# bigsegment.net
KiCad netlist of a schematic drawn in Altium Designer
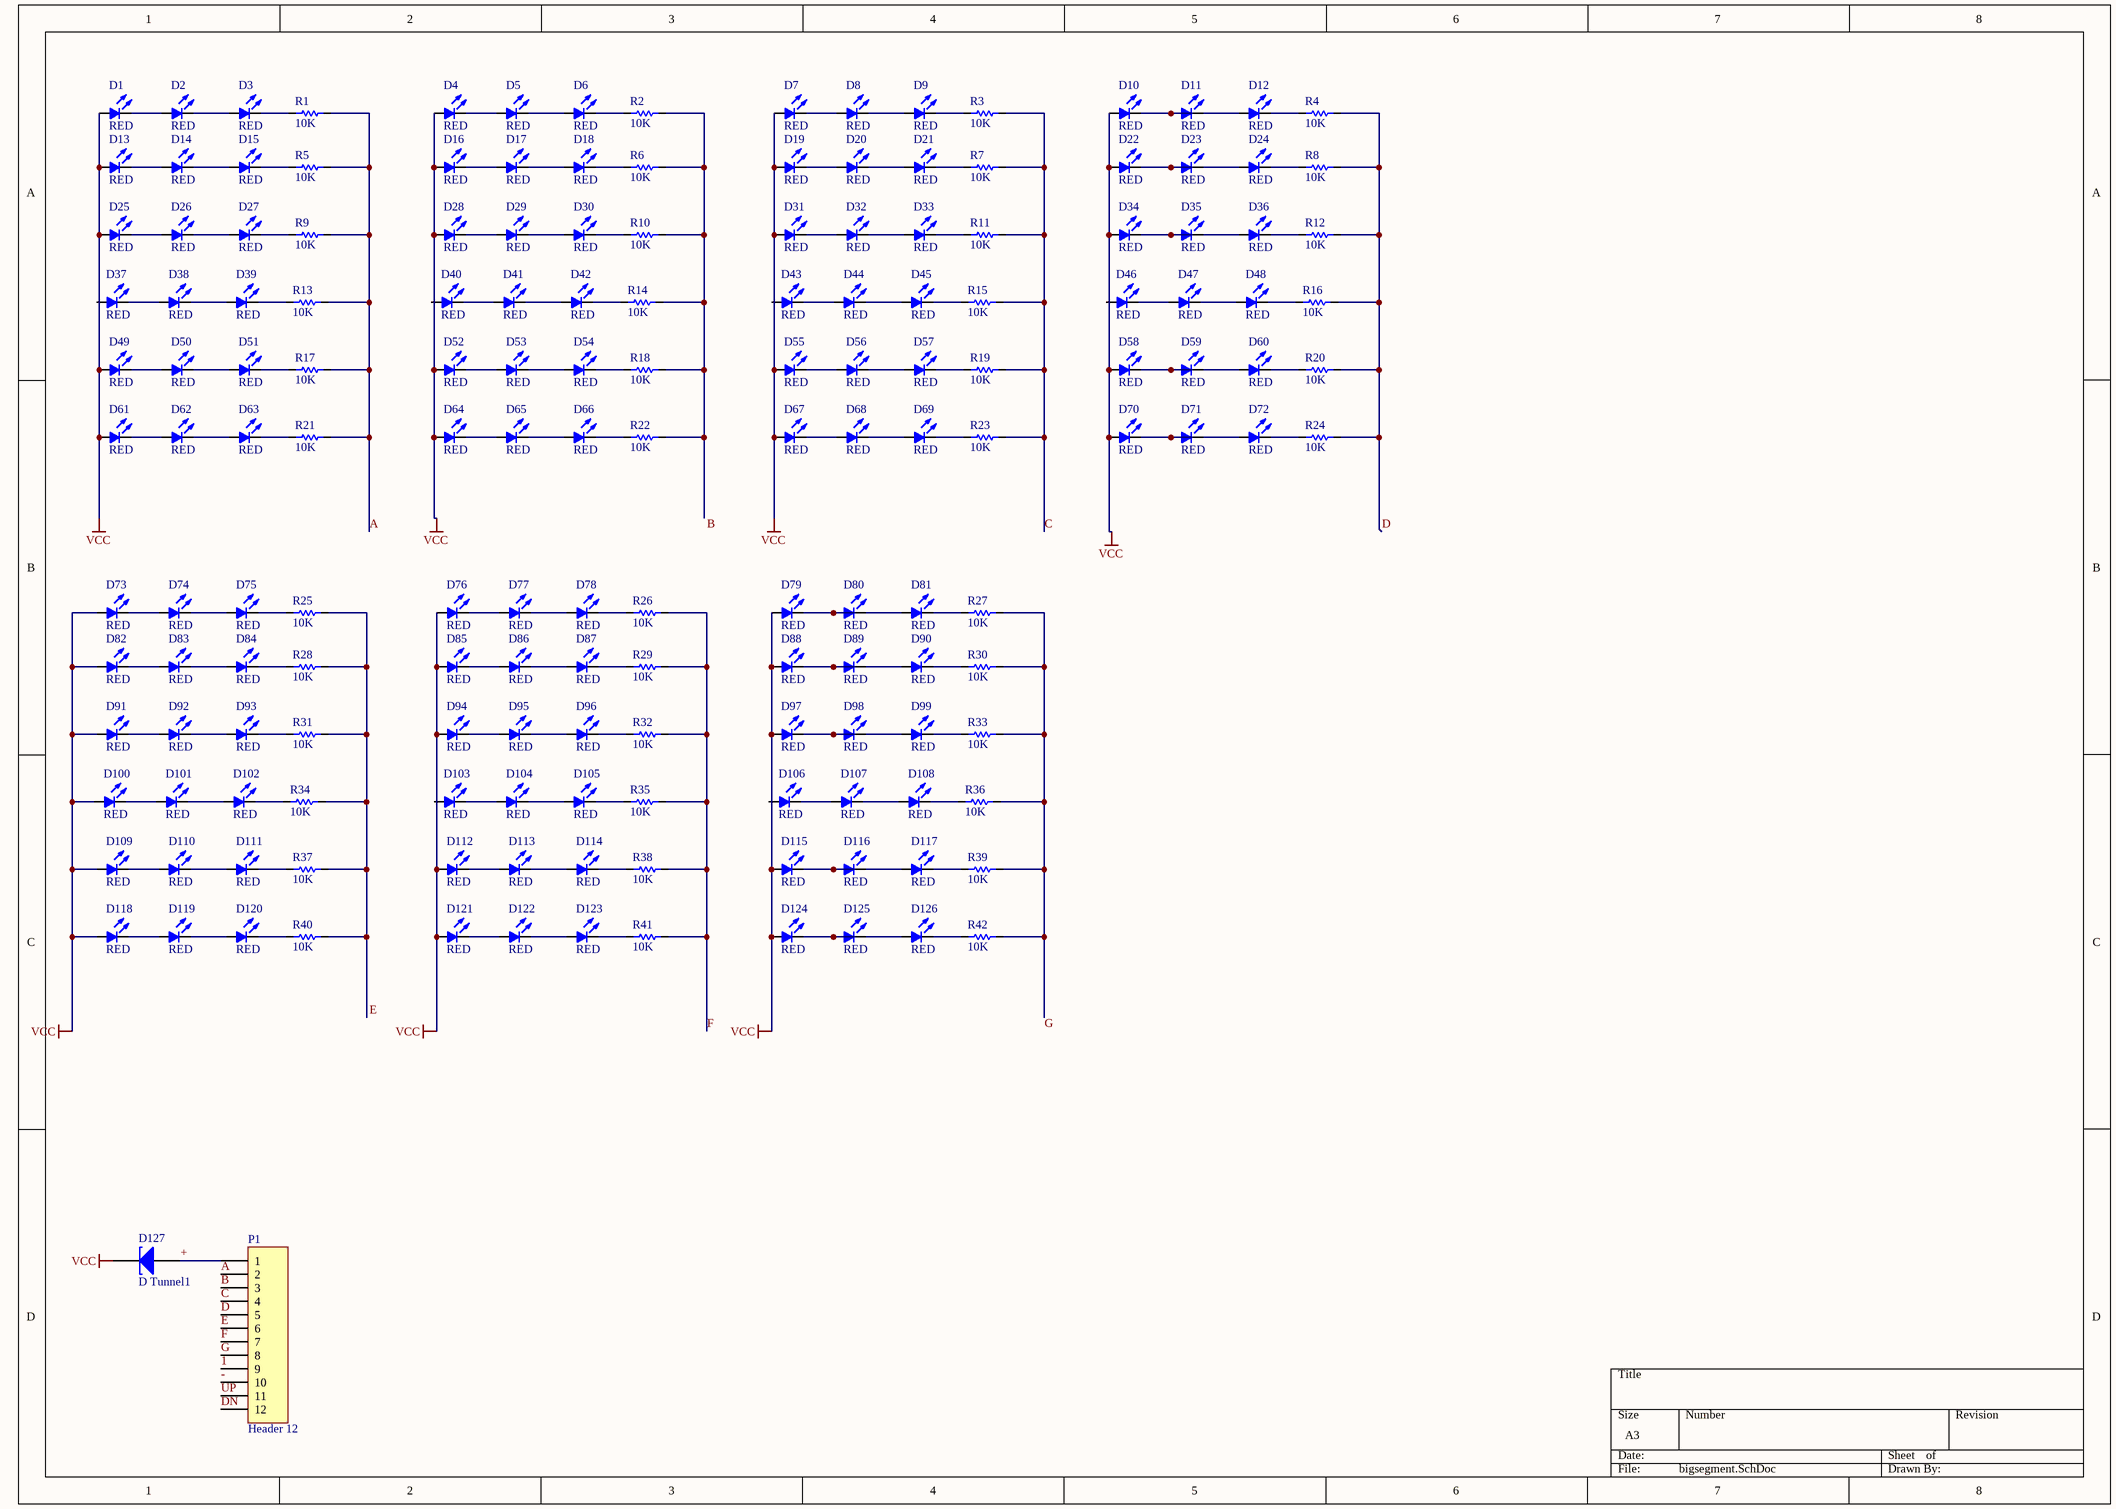
[diagram p0: bigsegment.SchDoc]

(export (version "E")
  (design (tool "Eeschema 10.0.6"))
  (components
    (comp (ref "D1")
      (value "MODEL")
      (footprint "RES 0805 (2012X06L)")
      (description "Typical LED")
      (fields (field (name "COLOR") "RED"))
      (libsource (lib "AltiumLib1") (part "LED 5mm"))
    )
    (comp (ref "D2")
      (value "MODEL")
      (footprint "RES 0805 (2012X06L)")
      (description "Typical LED")
      (fields (field (name "COLOR") "RED"))
      (libsource (lib "AltiumLib1") (part "LED 5mm"))
    )
    (comp (ref "D3")
      (value "MODEL")
      (footprint "RES 0805 (2012X06L)")
      (description "Typical LED")
      (fields (field (name "COLOR") "RED"))
      (libsource (lib "AltiumLib1") (part "LED 5mm"))
    )
    (comp (ref "D4")
      (value "MODEL")
      (footprint "RES 0805 (2012X06L)")
      (description "Typical LED")
      (fields (field (name "COLOR") "RED"))
      (libsource (lib "AltiumLib1") (part "LED 5mm"))
    )
    (comp (ref "D5")
      (value "MODEL")
      (footprint "RES 0805 (2012X06L)")
      (description "Typical LED")
      (fields (field (name "COLOR") "RED"))
      (libsource (lib "AltiumLib1") (part "LED 5mm"))
    )
    (comp (ref "D6")
      (value "MODEL")
      (footprint "RES 0805 (2012X06L)")
      (description "Typical LED")
      (fields (field (name "COLOR") "RED"))
      (libsource (lib "AltiumLib1") (part "LED 5mm"))
    )
    (comp (ref "D7")
      (value "MODEL")
      (footprint "RES 0805 (2012X06L)")
      (description "Typical LED")
      (fields (field (name "COLOR") "RED"))
      (libsource (lib "AltiumLib1") (part "LED 5mm"))
    )
    (comp (ref "D8")
      (value "MODEL")
      (footprint "RES 0805 (2012X06L)")
      (description "Typical LED")
      (fields (field (name "COLOR") "RED"))
      (libsource (lib "AltiumLib1") (part "LED 5mm"))
    )
    (comp (ref "D9")
      (value "MODEL")
      (footprint "RES 0805 (2012X06L)")
      (description "Typical LED")
      (fields (field (name "COLOR") "RED"))
      (libsource (lib "AltiumLib1") (part "LED 5mm"))
    )
    (comp (ref "D10")
      (value "MODEL")
      (footprint "RES 0805 (2012X06L)")
      (description "Typical LED")
      (fields (field (name "COLOR") "RED"))
      (libsource (lib "AltiumLib1") (part "LED 5mm"))
    )
    (comp (ref "D11")
      (value "MODEL")
      (footprint "RES 0805 (2012X06L)")
      (description "Typical LED")
      (fields (field (name "COLOR") "RED"))
      (libsource (lib "AltiumLib1") (part "LED 5mm"))
    )
    (comp (ref "D12")
      (value "MODEL")
      (footprint "RES 0805 (2012X06L)")
      (description "Typical LED")
      (fields (field (name "COLOR") "RED"))
      (libsource (lib "AltiumLib1") (part "LED 5mm"))
    )
    (comp (ref "D13")
      (value "MODEL")
      (footprint "RES 0805 (2012X06L)")
      (description "Typical LED")
      (fields (field (name "COLOR") "RED"))
      (libsource (lib "AltiumLib1") (part "LED 5mm"))
    )
    (comp (ref "D14")
      (value "MODEL")
      (footprint "RES 0805 (2012X06L)")
      (description "Typical LED")
      (fields (field (name "COLOR") "RED"))
      (libsource (lib "AltiumLib1") (part "LED 5mm"))
    )
    (comp (ref "D15")
      (value "MODEL")
      (footprint "RES 0805 (2012X06L)")
      (description "Typical LED")
      (fields (field (name "COLOR") "RED"))
      (libsource (lib "AltiumLib1") (part "LED 5mm"))
    )
    (comp (ref "D16")
      (value "MODEL")
      (footprint "RES 0805 (2012X06L)")
      (description "Typical LED")
      (fields (field (name "COLOR") "RED"))
      (libsource (lib "AltiumLib1") (part "LED 5mm"))
    )
    (comp (ref "D17")
      (value "MODEL")
      (footprint "RES 0805 (2012X06L)")
      (description "Typical LED")
      (fields (field (name "COLOR") "RED"))
      (libsource (lib "AltiumLib1") (part "LED 5mm"))
    )
    (comp (ref "D18")
      (value "MODEL")
      (footprint "RES 0805 (2012X06L)")
      (description "Typical LED")
      (fields (field (name "COLOR") "RED"))
      (libsource (lib "AltiumLib1") (part "LED 5mm"))
    )
    (comp (ref "D19")
      (value "MODEL")
      (footprint "RES 0805 (2012X06L)")
      (description "Typical LED")
      (fields (field (name "COLOR") "RED"))
      (libsource (lib "AltiumLib1") (part "LED 5mm"))
    )
    (comp (ref "D20")
      (value "MODEL")
      (footprint "RES 0805 (2012X06L)")
      (description "Typical LED")
      (fields (field (name "COLOR") "RED"))
      (libsource (lib "AltiumLib1") (part "LED 5mm"))
    )
    (comp (ref "D21")
      (value "MODEL")
      (footprint "RES 0805 (2012X06L)")
      (description "Typical LED")
      (fields (field (name "COLOR") "RED"))
      (libsource (lib "AltiumLib1") (part "LED 5mm"))
    )
    (comp (ref "D22")
      (value "MODEL")
      (footprint "RES 0805 (2012X06L)")
      (description "Typical LED")
      (fields (field (name "COLOR") "RED"))
      (libsource (lib "AltiumLib1") (part "LED 5mm"))
    )
    (comp (ref "D23")
      (value "MODEL")
      (footprint "RES 0805 (2012X06L)")
      (description "Typical LED")
      (fields (field (name "COLOR") "RED"))
      (libsource (lib "AltiumLib1") (part "LED 5mm"))
    )
    (comp (ref "D24")
      (value "MODEL")
      (footprint "RES 0805 (2012X06L)")
      (description "Typical LED")
      (fields (field (name "COLOR") "RED"))
      (libsource (lib "AltiumLib1") (part "LED 5mm"))
    )
    (comp (ref "D25")
      (value "MODEL")
      (footprint "RES 0805 (2012X06L)")
      (description "Typical LED")
      (fields (field (name "COLOR") "RED"))
      (libsource (lib "AltiumLib1") (part "LED 5mm"))
    )
    (comp (ref "D26")
      (value "MODEL")
      (footprint "RES 0805 (2012X06L)")
      (description "Typical LED")
      (fields (field (name "COLOR") "RED"))
      (libsource (lib "AltiumLib1") (part "LED 5mm"))
    )
    (comp (ref "D27")
      (value "MODEL")
      (footprint "RES 0805 (2012X06L)")
      (description "Typical LED")
      (fields (field (name "COLOR") "RED"))
      (libsource (lib "AltiumLib1") (part "LED 5mm"))
    )
    (comp (ref "D28")
      (value "MODEL")
      (footprint "RES 0805 (2012X06L)")
      (description "Typical LED")
      (fields (field (name "COLOR") "RED"))
      (libsource (lib "AltiumLib1") (part "LED 5mm"))
    )
    (comp (ref "D29")
      (value "MODEL")
      (footprint "RES 0805 (2012X06L)")
      (description "Typical LED")
      (fields (field (name "COLOR") "RED"))
      (libsource (lib "AltiumLib1") (part "LED 5mm"))
    )
    (comp (ref "D30")
      (value "MODEL")
      (footprint "RES 0805 (2012X06L)")
      (description "Typical LED")
      (fields (field (name "COLOR") "RED"))
      (libsource (lib "AltiumLib1") (part "LED 5mm"))
    )
    (comp (ref "D31")
      (value "MODEL")
      (footprint "RES 0805 (2012X06L)")
      (description "Typical LED")
      (fields (field (name "COLOR") "RED"))
      (libsource (lib "AltiumLib1") (part "LED 5mm"))
    )
    (comp (ref "D32")
      (value "MODEL")
      (footprint "RES 0805 (2012X06L)")
      (description "Typical LED")
      (fields (field (name "COLOR") "RED"))
      (libsource (lib "AltiumLib1") (part "LED 5mm"))
    )
    (comp (ref "D33")
      (value "MODEL")
      (footprint "RES 0805 (2012X06L)")
      (description "Typical LED")
      (fields (field (name "COLOR") "RED"))
      (libsource (lib "AltiumLib1") (part "LED 5mm"))
    )
    (comp (ref "D34")
      (value "MODEL")
      (footprint "RES 0805 (2012X06L)")
      (description "Typical LED")
      (fields (field (name "COLOR") "RED"))
      (libsource (lib "AltiumLib1") (part "LED 5mm"))
    )
    (comp (ref "D35")
      (value "MODEL")
      (footprint "RES 0805 (2012X06L)")
      (description "Typical LED")
      (fields (field (name "COLOR") "RED"))
      (libsource (lib "AltiumLib1") (part "LED 5mm"))
    )
    (comp (ref "D36")
      (value "MODEL")
      (footprint "RES 0805 (2012X06L)")
      (description "Typical LED")
      (fields (field (name "COLOR") "RED"))
      (libsource (lib "AltiumLib1") (part "LED 5mm"))
    )
    (comp (ref "D37")
      (value "MODEL")
      (footprint "RES 0805 (2012X06L)")
      (description "Typical LED")
      (fields (field (name "COLOR") "RED"))
      (libsource (lib "AltiumLib1") (part "LED 5mm"))
    )
    (comp (ref "D38")
      (value "MODEL")
      (footprint "RES 0805 (2012X06L)")
      (description "Typical LED")
      (fields (field (name "COLOR") "RED"))
      (libsource (lib "AltiumLib1") (part "LED 5mm"))
    )
    (comp (ref "D39")
      (value "MODEL")
      (footprint "RES 0805 (2012X06L)")
      (description "Typical LED")
      (fields (field (name "COLOR") "RED"))
      (libsource (lib "AltiumLib1") (part "LED 5mm"))
    )
    (comp (ref "D40")
      (value "MODEL")
      (footprint "RES 0805 (2012X06L)")
      (description "Typical LED")
      (fields (field (name "COLOR") "RED"))
      (libsource (lib "AltiumLib1") (part "LED 5mm"))
    )
    (comp (ref "D41")
      (value "MODEL")
      (footprint "RES 0805 (2012X06L)")
      (description "Typical LED")
      (fields (field (name "COLOR") "RED"))
      (libsource (lib "AltiumLib1") (part "LED 5mm"))
    )
    (comp (ref "D42")
      (value "MODEL")
      (footprint "RES 0805 (2012X06L)")
      (description "Typical LED")
      (fields (field (name "COLOR") "RED"))
      (libsource (lib "AltiumLib1") (part "LED 5mm"))
    )
    (comp (ref "D43")
      (value "MODEL")
      (footprint "RES 0805 (2012X06L)")
      (description "Typical LED")
      (fields (field (name "COLOR") "RED"))
      (libsource (lib "AltiumLib1") (part "LED 5mm"))
    )
    (comp (ref "D44")
      (value "MODEL")
      (footprint "RES 0805 (2012X06L)")
      (description "Typical LED")
      (fields (field (name "COLOR") "RED"))
      (libsource (lib "AltiumLib1") (part "LED 5mm"))
    )
    (comp (ref "D45")
      (value "MODEL")
      (footprint "RES 0805 (2012X06L)")
      (description "Typical LED")
      (fields (field (name "COLOR") "RED"))
      (libsource (lib "AltiumLib1") (part "LED 5mm"))
    )
    (comp (ref "D46")
      (value "MODEL")
      (footprint "RES 0805 (2012X06L)")
      (description "Typical LED")
      (fields (field (name "COLOR") "RED"))
      (libsource (lib "AltiumLib1") (part "LED 5mm"))
    )
    (comp (ref "D47")
      (value "MODEL")
      (footprint "RES 0805 (2012X06L)")
      (description "Typical LED")
      (fields (field (name "COLOR") "RED"))
      (libsource (lib "AltiumLib1") (part "LED 5mm"))
    )
    (comp (ref "D48")
      (value "MODEL")
      (footprint "RES 0805 (2012X06L)")
      (description "Typical LED")
      (fields (field (name "COLOR") "RED"))
      (libsource (lib "AltiumLib1") (part "LED 5mm"))
    )
    (comp (ref "D49")
      (value "MODEL")
      (footprint "RES 0805 (2012X06L)")
      (description "Typical LED")
      (fields (field (name "COLOR") "RED"))
      (libsource (lib "AltiumLib1") (part "LED 5mm"))
    )
    (comp (ref "D50")
      (value "MODEL")
      (footprint "RES 0805 (2012X06L)")
      (description "Typical LED")
      (fields (field (name "COLOR") "RED"))
      (libsource (lib "AltiumLib1") (part "LED 5mm"))
    )
    (comp (ref "D51")
      (value "MODEL")
      (footprint "RES 0805 (2012X06L)")
      (description "Typical LED")
      (fields (field (name "COLOR") "RED"))
      (libsource (lib "AltiumLib1") (part "LED 5mm"))
    )
    (comp (ref "D52")
      (value "MODEL")
      (footprint "RES 0805 (2012X06L)")
      (description "Typical LED")
      (fields (field (name "COLOR") "RED"))
      (libsource (lib "AltiumLib1") (part "LED 5mm"))
    )
    (comp (ref "D53")
      (value "MODEL")
      (footprint "RES 0805 (2012X06L)")
      (description "Typical LED")
      (fields (field (name "COLOR") "RED"))
      (libsource (lib "AltiumLib1") (part "LED 5mm"))
    )
    (comp (ref "D54")
      (value "MODEL")
      (footprint "RES 0805 (2012X06L)")
      (description "Typical LED")
      (fields (field (name "COLOR") "RED"))
      (libsource (lib "AltiumLib1") (part "LED 5mm"))
    )
    (comp (ref "D55")
      (value "MODEL")
      (footprint "RES 0805 (2012X06L)")
      (description "Typical LED")
      (fields (field (name "COLOR") "RED"))
      (libsource (lib "AltiumLib1") (part "LED 5mm"))
    )
    (comp (ref "D56")
      (value "MODEL")
      (footprint "RES 0805 (2012X06L)")
      (description "Typical LED")
      (fields (field (name "COLOR") "RED"))
      (libsource (lib "AltiumLib1") (part "LED 5mm"))
    )
    (comp (ref "D57")
      (value "MODEL")
      (footprint "RES 0805 (2012X06L)")
      (description "Typical LED")
      (fields (field (name "COLOR") "RED"))
      (libsource (lib "AltiumLib1") (part "LED 5mm"))
    )
    (comp (ref "D58")
      (value "MODEL")
      (footprint "RES 0805 (2012X06L)")
      (description "Typical LED")
      (fields (field (name "COLOR") "RED"))
      (libsource (lib "AltiumLib1") (part "LED 5mm"))
    )
    (comp (ref "D59")
      (value "MODEL")
      (footprint "RES 0805 (2012X06L)")
      (description "Typical LED")
      (fields (field (name "COLOR") "RED"))
      (libsource (lib "AltiumLib1") (part "LED 5mm"))
    )
    (comp (ref "D60")
      (value "MODEL")
      (footprint "RES 0805 (2012X06L)")
      (description "Typical LED")
      (fields (field (name "COLOR") "RED"))
      (libsource (lib "AltiumLib1") (part "LED 5mm"))
    )
    (comp (ref "D61")
      (value "MODEL")
      (footprint "RES 0805 (2012X06L)")
      (description "Typical LED")
      (fields (field (name "COLOR") "RED"))
      (libsource (lib "AltiumLib1") (part "LED 5mm"))
    )
    (comp (ref "D62")
      (value "MODEL")
      (footprint "RES 0805 (2012X06L)")
      (description "Typical LED")
      (fields (field (name "COLOR") "RED"))
      (libsource (lib "AltiumLib1") (part "LED 5mm"))
    )
    (comp (ref "D63")
      (value "MODEL")
      (footprint "RES 0805 (2012X06L)")
      (description "Typical LED")
      (fields (field (name "COLOR") "RED"))
      (libsource (lib "AltiumLib1") (part "LED 5mm"))
    )
    (comp (ref "D64")
      (value "MODEL")
      (footprint "RES 0805 (2012X06L)")
      (description "Typical LED")
      (fields (field (name "COLOR") "RED"))
      (libsource (lib "AltiumLib1") (part "LED 5mm"))
    )
    (comp (ref "D65")
      (value "MODEL")
      (footprint "RES 0805 (2012X06L)")
      (description "Typical LED")
      (fields (field (name "COLOR") "RED"))
      (libsource (lib "AltiumLib1") (part "LED 5mm"))
    )
    (comp (ref "D66")
      (value "MODEL")
      (footprint "RES 0805 (2012X06L)")
      (description "Typical LED")
      (fields (field (name "COLOR") "RED"))
      (libsource (lib "AltiumLib1") (part "LED 5mm"))
    )
    (comp (ref "D67")
      (value "MODEL")
      (footprint "RES 0805 (2012X06L)")
      (description "Typical LED")
      (fields (field (name "COLOR") "RED"))
      (libsource (lib "AltiumLib1") (part "LED 5mm"))
    )
    (comp (ref "D68")
      (value "MODEL")
      (footprint "RES 0805 (2012X06L)")
      (description "Typical LED")
      (fields (field (name "COLOR") "RED"))
      (libsource (lib "AltiumLib1") (part "LED 5mm"))
    )
    (comp (ref "D69")
      (value "MODEL")
      (footprint "RES 0805 (2012X06L)")
      (description "Typical LED")
      (fields (field (name "COLOR") "RED"))
      (libsource (lib "AltiumLib1") (part "LED 5mm"))
    )
    (comp (ref "D70")
      (value "MODEL")
      (footprint "RES 0805 (2012X06L)")
      (description "Typical LED")
      (fields (field (name "COLOR") "RED"))
      (libsource (lib "AltiumLib1") (part "LED 5mm"))
    )
    (comp (ref "D71")
      (value "MODEL")
      (footprint "RES 0805 (2012X06L)")
      (description "Typical LED")
      (fields (field (name "COLOR") "RED"))
      (libsource (lib "AltiumLib1") (part "LED 5mm"))
    )
    (comp (ref "D72")
      (value "MODEL")
      (footprint "RES 0805 (2012X06L)")
      (description "Typical LED")
      (fields (field (name "COLOR") "RED"))
      (libsource (lib "AltiumLib1") (part "LED 5mm"))
    )
    (comp (ref "D73")
      (value "MODEL")
      (footprint "RES 0805 (2012X06L)")
      (description "Typical LED")
      (fields (field (name "COLOR") "RED"))
      (libsource (lib "AltiumLib1") (part "LED 5mm"))
    )
    (comp (ref "D74")
      (value "MODEL")
      (footprint "RES 0805 (2012X06L)")
      (description "Typical LED")
      (fields (field (name "COLOR") "RED"))
      (libsource (lib "AltiumLib1") (part "LED 5mm"))
    )
    (comp (ref "D75")
      (value "MODEL")
      (footprint "RES 0805 (2012X06L)")
      (description "Typical LED")
      (fields (field (name "COLOR") "RED"))
      (libsource (lib "AltiumLib1") (part "LED 5mm"))
    )
    (comp (ref "D76")
      (value "MODEL")
      (footprint "RES 0805 (2012X06L)")
      (description "Typical LED")
      (fields (field (name "COLOR") "RED"))
      (libsource (lib "AltiumLib1") (part "LED 5mm"))
    )
    (comp (ref "D77")
      (value "MODEL")
      (footprint "RES 0805 (2012X06L)")
      (description "Typical LED")
      (fields (field (name "COLOR") "RED"))
      (libsource (lib "AltiumLib1") (part "LED 5mm"))
    )
    (comp (ref "D78")
      (value "MODEL")
      (footprint "RES 0805 (2012X06L)")
      (description "Typical LED")
      (fields (field (name "COLOR") "RED"))
      (libsource (lib "AltiumLib1") (part "LED 5mm"))
    )
    (comp (ref "D79")
      (value "MODEL")
      (footprint "RES 0805 (2012X06L)")
      (description "Typical LED")
      (fields (field (name "COLOR") "RED"))
      (libsource (lib "AltiumLib1") (part "LED 5mm"))
    )
    (comp (ref "D80")
      (value "MODEL")
      (footprint "RES 0805 (2012X06L)")
      (description "Typical LED")
      (fields (field (name "COLOR") "RED"))
      (libsource (lib "AltiumLib1") (part "LED 5mm"))
    )
    (comp (ref "D81")
      (value "MODEL")
      (footprint "RES 0805 (2012X06L)")
      (description "Typical LED")
      (fields (field (name "COLOR") "RED"))
      (libsource (lib "AltiumLib1") (part "LED 5mm"))
    )
    (comp (ref "D82")
      (value "MODEL")
      (footprint "RES 0805 (2012X06L)")
      (description "Typical LED")
      (fields (field (name "COLOR") "RED"))
      (libsource (lib "AltiumLib1") (part "LED 5mm"))
    )
    (comp (ref "D83")
      (value "MODEL")
      (footprint "RES 0805 (2012X06L)")
      (description "Typical LED")
      (fields (field (name "COLOR") "RED"))
      (libsource (lib "AltiumLib1") (part "LED 5mm"))
    )
    (comp (ref "D84")
      (value "MODEL")
      (footprint "RES 0805 (2012X06L)")
      (description "Typical LED")
      (fields (field (name "COLOR") "RED"))
      (libsource (lib "AltiumLib1") (part "LED 5mm"))
    )
    (comp (ref "D85")
      (value "MODEL")
      (footprint "RES 0805 (2012X06L)")
      (description "Typical LED")
      (fields (field (name "COLOR") "RED"))
      (libsource (lib "AltiumLib1") (part "LED 5mm"))
    )
    (comp (ref "D86")
      (value "MODEL")
      (footprint "RES 0805 (2012X06L)")
      (description "Typical LED")
      (fields (field (name "COLOR") "RED"))
      (libsource (lib "AltiumLib1") (part "LED 5mm"))
    )
    (comp (ref "D87")
      (value "MODEL")
      (footprint "RES 0805 (2012X06L)")
      (description "Typical LED")
      (fields (field (name "COLOR") "RED"))
      (libsource (lib "AltiumLib1") (part "LED 5mm"))
    )
    (comp (ref "D88")
      (value "MODEL")
      (footprint "RES 0805 (2012X06L)")
      (description "Typical LED")
      (fields (field (name "COLOR") "RED"))
      (libsource (lib "AltiumLib1") (part "LED 5mm"))
    )
    (comp (ref "D89")
      (value "MODEL")
      (footprint "RES 0805 (2012X06L)")
      (description "Typical LED")
      (fields (field (name "COLOR") "RED"))
      (libsource (lib "AltiumLib1") (part "LED 5mm"))
    )
    (comp (ref "D90")
      (value "MODEL")
      (footprint "RES 0805 (2012X06L)")
      (description "Typical LED")
      (fields (field (name "COLOR") "RED"))
      (libsource (lib "AltiumLib1") (part "LED 5mm"))
    )
    (comp (ref "D91")
      (value "MODEL")
      (footprint "RES 0805 (2012X06L)")
      (description "Typical LED")
      (fields (field (name "COLOR") "RED"))
      (libsource (lib "AltiumLib1") (part "LED 5mm"))
    )
    (comp (ref "D92")
      (value "MODEL")
      (footprint "RES 0805 (2012X06L)")
      (description "Typical LED")
      (fields (field (name "COLOR") "RED"))
      (libsource (lib "AltiumLib1") (part "LED 5mm"))
    )
    (comp (ref "D93")
      (value "MODEL")
      (footprint "RES 0805 (2012X06L)")
      (description "Typical LED")
      (fields (field (name "COLOR") "RED"))
      (libsource (lib "AltiumLib1") (part "LED 5mm"))
    )
    (comp (ref "D94")
      (value "MODEL")
      (footprint "RES 0805 (2012X06L)")
      (description "Typical LED")
      (fields (field (name "COLOR") "RED"))
      (libsource (lib "AltiumLib1") (part "LED 5mm"))
    )
    (comp (ref "D95")
      (value "MODEL")
      (footprint "RES 0805 (2012X06L)")
      (description "Typical LED")
      (fields (field (name "COLOR") "RED"))
      (libsource (lib "AltiumLib1") (part "LED 5mm"))
    )
    (comp (ref "D96")
      (value "MODEL")
      (footprint "RES 0805 (2012X06L)")
      (description "Typical LED")
      (fields (field (name "COLOR") "RED"))
      (libsource (lib "AltiumLib1") (part "LED 5mm"))
    )
    (comp (ref "D97")
      (value "MODEL")
      (footprint "RES 0805 (2012X06L)")
      (description "Typical LED")
      (fields (field (name "COLOR") "RED"))
      (libsource (lib "AltiumLib1") (part "LED 5mm"))
    )
    (comp (ref "D98")
      (value "MODEL")
      (footprint "RES 0805 (2012X06L)")
      (description "Typical LED")
      (fields (field (name "COLOR") "RED"))
      (libsource (lib "AltiumLib1") (part "LED 5mm"))
    )
    (comp (ref "D99")
      (value "MODEL")
      (footprint "RES 0805 (2012X06L)")
      (description "Typical LED")
      (fields (field (name "COLOR") "RED"))
      (libsource (lib "AltiumLib1") (part "LED 5mm"))
    )
    (comp (ref "D100")
      (value "MODEL")
      (footprint "RES 0805 (2012X06L)")
      (description "Typical LED")
      (fields (field (name "COLOR") "RED"))
      (libsource (lib "AltiumLib1") (part "LED 5mm"))
    )
    (comp (ref "D101")
      (value "MODEL")
      (footprint "RES 0805 (2012X06L)")
      (description "Typical LED")
      (fields (field (name "COLOR") "RED"))
      (libsource (lib "AltiumLib1") (part "LED 5mm"))
    )
    (comp (ref "D102")
      (value "MODEL")
      (footprint "RES 0805 (2012X06L)")
      (description "Typical LED")
      (fields (field (name "COLOR") "RED"))
      (libsource (lib "AltiumLib1") (part "LED 5mm"))
    )
    (comp (ref "D103")
      (value "MODEL")
      (footprint "RES 0805 (2012X06L)")
      (description "Typical LED")
      (fields (field (name "COLOR") "RED"))
      (libsource (lib "AltiumLib1") (part "LED 5mm"))
    )
    (comp (ref "D104")
      (value "MODEL")
      (footprint "RES 0805 (2012X06L)")
      (description "Typical LED")
      (fields (field (name "COLOR") "RED"))
      (libsource (lib "AltiumLib1") (part "LED 5mm"))
    )
    (comp (ref "D105")
      (value "MODEL")
      (footprint "RES 0805 (2012X06L)")
      (description "Typical LED")
      (fields (field (name "COLOR") "RED"))
      (libsource (lib "AltiumLib1") (part "LED 5mm"))
    )
    (comp (ref "D106")
      (value "MODEL")
      (footprint "RES 0805 (2012X06L)")
      (description "Typical LED")
      (fields (field (name "COLOR") "RED"))
      (libsource (lib "AltiumLib1") (part "LED 5mm"))
    )
    (comp (ref "D107")
      (value "MODEL")
      (footprint "RES 0805 (2012X06L)")
      (description "Typical LED")
      (fields (field (name "COLOR") "RED"))
      (libsource (lib "AltiumLib1") (part "LED 5mm"))
    )
    (comp (ref "D108")
      (value "MODEL")
      (footprint "RES 0805 (2012X06L)")
      (description "Typical LED")
      (fields (field (name "COLOR") "RED"))
      (libsource (lib "AltiumLib1") (part "LED 5mm"))
    )
    (comp (ref "D109")
      (value "MODEL")
      (footprint "RES 0805 (2012X06L)")
      (description "Typical LED")
      (fields (field (name "COLOR") "RED"))
      (libsource (lib "AltiumLib1") (part "LED 5mm"))
    )
    (comp (ref "D110")
      (value "MODEL")
      (footprint "RES 0805 (2012X06L)")
      (description "Typical LED")
      (fields (field (name "COLOR") "RED"))
      (libsource (lib "AltiumLib1") (part "LED 5mm"))
    )
    (comp (ref "D111")
      (value "MODEL")
      (footprint "RES 0805 (2012X06L)")
      (description "Typical LED")
      (fields (field (name "COLOR") "RED"))
      (libsource (lib "AltiumLib1") (part "LED 5mm"))
    )
    (comp (ref "D112")
      (value "MODEL")
      (footprint "RES 0805 (2012X06L)")
      (description "Typical LED")
      (fields (field (name "COLOR") "RED"))
      (libsource (lib "AltiumLib1") (part "LED 5mm"))
    )
    (comp (ref "D113")
      (value "MODEL")
      (footprint "RES 0805 (2012X06L)")
      (description "Typical LED")
      (fields (field (name "COLOR") "RED"))
      (libsource (lib "AltiumLib1") (part "LED 5mm"))
    )
    (comp (ref "D114")
      (value "MODEL")
      (footprint "RES 0805 (2012X06L)")
      (description "Typical LED")
      (fields (field (name "COLOR") "RED"))
      (libsource (lib "AltiumLib1") (part "LED 5mm"))
    )
    (comp (ref "D115")
      (value "MODEL")
      (footprint "RES 0805 (2012X06L)")
      (description "Typical LED")
      (fields (field (name "COLOR") "RED"))
      (libsource (lib "AltiumLib1") (part "LED 5mm"))
    )
    (comp (ref "D116")
      (value "MODEL")
      (footprint "RES 0805 (2012X06L)")
      (description "Typical LED")
      (fields (field (name "COLOR") "RED"))
      (libsource (lib "AltiumLib1") (part "LED 5mm"))
    )
    (comp (ref "D117")
      (value "MODEL")
      (footprint "RES 0805 (2012X06L)")
      (description "Typical LED")
      (fields (field (name "COLOR") "RED"))
      (libsource (lib "AltiumLib1") (part "LED 5mm"))
    )
    (comp (ref "D118")
      (value "MODEL")
      (footprint "RES 0805 (2012X06L)")
      (description "Typical LED")
      (fields (field (name "COLOR") "RED"))
      (libsource (lib "AltiumLib1") (part "LED 5mm"))
    )
    (comp (ref "D119")
      (value "MODEL")
      (footprint "RES 0805 (2012X06L)")
      (description "Typical LED")
      (fields (field (name "COLOR") "RED"))
      (libsource (lib "AltiumLib1") (part "LED 5mm"))
    )
    (comp (ref "D120")
      (value "MODEL")
      (footprint "RES 0805 (2012X06L)")
      (description "Typical LED")
      (fields (field (name "COLOR") "RED"))
      (libsource (lib "AltiumLib1") (part "LED 5mm"))
    )
    (comp (ref "D121")
      (value "MODEL")
      (footprint "RES 0805 (2012X06L)")
      (description "Typical LED")
      (fields (field (name "COLOR") "RED"))
      (libsource (lib "AltiumLib1") (part "LED 5mm"))
    )
    (comp (ref "D122")
      (value "MODEL")
      (footprint "RES 0805 (2012X06L)")
      (description "Typical LED")
      (fields (field (name "COLOR") "RED"))
      (libsource (lib "AltiumLib1") (part "LED 5mm"))
    )
    (comp (ref "D123")
      (value "MODEL")
      (footprint "RES 0805 (2012X06L)")
      (description "Typical LED")
      (fields (field (name "COLOR") "RED"))
      (libsource (lib "AltiumLib1") (part "LED 5mm"))
    )
    (comp (ref "D124")
      (value "MODEL")
      (footprint "RES 0805 (2012X06L)")
      (description "Typical LED")
      (fields (field (name "COLOR") "RED"))
      (libsource (lib "AltiumLib1") (part "LED 5mm"))
    )
    (comp (ref "D125")
      (value "MODEL")
      (footprint "RES 0805 (2012X06L)")
      (description "Typical LED")
      (fields (field (name "COLOR") "RED"))
      (libsource (lib "AltiumLib1") (part "LED 5mm"))
    )
    (comp (ref "D126")
      (value "MODEL")
      (footprint "RES 0805 (2012X06L)")
      (description "Typical LED")
      (fields (field (name "COLOR") "RED"))
      (libsource (lib "AltiumLib1") (part "LED 5mm"))
    )
    (comp (ref "D127")
      (value "D Tunnel1")
      (footprint "3.2X1.6X1.1")
      (description "Tunnel Diode - RLC Model")
      (fields (field (name "PUBLISHER") "Altium Limited"))
      (libsource (lib "Miscellaneous Devices") (part "D Tunnel1"))
    )
    (comp (ref "P1")
      (value "Header 12")
      (footprint "HDR1X12")
      (description "Header, 12-Pin")
      (fields (field (name "PUBLISHER") "Altium Limited"))
      (libsource (lib "Miscellaneous Connectors") (part "Header 12"))
    )
    (comp (ref "R1")
      (value "10K")
      (footprint "RES 1206 (3216X08L)")
      (description "Resistor")
      (fields (field (name "TOLERANCE") "5%") (field (name "POWER") "1/4 W"))
      (libsource (lib "AltiumLib1") (part "Resistor"))
    )
    (comp (ref "R2")
      (value "10K")
      (footprint "RES 1206 (3216X08L)")
      (description "Resistor")
      (fields (field (name "TOLERANCE") "5%") (field (name "POWER") "1/4 W"))
      (libsource (lib "AltiumLib1") (part "Resistor"))
    )
    (comp (ref "R3")
      (value "10K")
      (footprint "RES 1206 (3216X08L)")
      (description "Resistor")
      (fields (field (name "TOLERANCE") "5%") (field (name "POWER") "1/4 W"))
      (libsource (lib "AltiumLib1") (part "Resistor"))
    )
    (comp (ref "R4")
      (value "10K")
      (footprint "RES 1206 (3216X08L)")
      (description "Resistor")
      (fields (field (name "TOLERANCE") "5%") (field (name "POWER") "1/4 W"))
      (libsource (lib "AltiumLib1") (part "Resistor"))
    )
    (comp (ref "R5")
      (value "10K")
      (footprint "RES 1206 (3216X08L)")
      (description "Resistor")
      (fields (field (name "TOLERANCE") "5%") (field (name "POWER") "1/4 W"))
      (libsource (lib "AltiumLib1") (part "Resistor"))
    )
    (comp (ref "R6")
      (value "10K")
      (footprint "RES 1206 (3216X08L)")
      (description "Resistor")
      (fields (field (name "TOLERANCE") "5%") (field (name "POWER") "1/4 W"))
      (libsource (lib "AltiumLib1") (part "Resistor"))
    )
    (comp (ref "R7")
      (value "10K")
      (footprint "RES 1206 (3216X08L)")
      (description "Resistor")
      (fields (field (name "TOLERANCE") "5%") (field (name "POWER") "1/4 W"))
      (libsource (lib "AltiumLib1") (part "Resistor"))
    )
    (comp (ref "R8")
      (value "10K")
      (footprint "RES 1206 (3216X08L)")
      (description "Resistor")
      (fields (field (name "TOLERANCE") "5%") (field (name "POWER") "1/4 W"))
      (libsource (lib "AltiumLib1") (part "Resistor"))
    )
    (comp (ref "R9")
      (value "10K")
      (footprint "RES 1206 (3216X08L)")
      (description "Resistor")
      (fields (field (name "TOLERANCE") "5%") (field (name "POWER") "1/4 W"))
      (libsource (lib "AltiumLib1") (part "Resistor"))
    )
    (comp (ref "R10")
      (value "10K")
      (footprint "RES 1206 (3216X08L)")
      (description "Resistor")
      (fields (field (name "TOLERANCE") "5%") (field (name "POWER") "1/4 W"))
      (libsource (lib "AltiumLib1") (part "Resistor"))
    )
    (comp (ref "R11")
      (value "10K")
      (footprint "RES 1206 (3216X08L)")
      (description "Resistor")
      (fields (field (name "TOLERANCE") "5%") (field (name "POWER") "1/4 W"))
      (libsource (lib "AltiumLib1") (part "Resistor"))
    )
    (comp (ref "R12")
      (value "10K")
      (footprint "RES 1206 (3216X08L)")
      (description "Resistor")
      (fields (field (name "TOLERANCE") "5%") (field (name "POWER") "1/4 W"))
      (libsource (lib "AltiumLib1") (part "Resistor"))
    )
    (comp (ref "R13")
      (value "10K")
      (footprint "RES 1206 (3216X08L)")
      (description "Resistor")
      (fields (field (name "TOLERANCE") "5%") (field (name "POWER") "1/4 W"))
      (libsource (lib "AltiumLib1") (part "Resistor"))
    )
    (comp (ref "R14")
      (value "10K")
      (footprint "RES 1206 (3216X08L)")
      (description "Resistor")
      (fields (field (name "TOLERANCE") "5%") (field (name "POWER") "1/4 W"))
      (libsource (lib "AltiumLib1") (part "Resistor"))
    )
    (comp (ref "R15")
      (value "10K")
      (footprint "RES 1206 (3216X08L)")
      (description "Resistor")
      (fields (field (name "TOLERANCE") "5%") (field (name "POWER") "1/4 W"))
      (libsource (lib "AltiumLib1") (part "Resistor"))
    )
    (comp (ref "R16")
      (value "10K")
      (footprint "RES 1206 (3216X08L)")
      (description "Resistor")
      (fields (field (name "TOLERANCE") "5%") (field (name "POWER") "1/4 W"))
      (libsource (lib "AltiumLib1") (part "Resistor"))
    )
    (comp (ref "R17")
      (value "10K")
      (footprint "RES 1206 (3216X08L)")
      (description "Resistor")
      (fields (field (name "TOLERANCE") "5%") (field (name "POWER") "1/4 W"))
      (libsource (lib "AltiumLib1") (part "Resistor"))
    )
    (comp (ref "R18")
      (value "10K")
      (footprint "RES 1206 (3216X08L)")
      (description "Resistor")
      (fields (field (name "TOLERANCE") "5%") (field (name "POWER") "1/4 W"))
      (libsource (lib "AltiumLib1") (part "Resistor"))
    )
    (comp (ref "R19")
      (value "10K")
      (footprint "RES 1206 (3216X08L)")
      (description "Resistor")
      (fields (field (name "TOLERANCE") "5%") (field (name "POWER") "1/4 W"))
      (libsource (lib "AltiumLib1") (part "Resistor"))
    )
    (comp (ref "R20")
      (value "10K")
      (footprint "RES 1206 (3216X08L)")
      (description "Resistor")
      (fields (field (name "TOLERANCE") "5%") (field (name "POWER") "1/4 W"))
      (libsource (lib "AltiumLib1") (part "Resistor"))
    )
    (comp (ref "R21")
      (value "10K")
      (footprint "RES 1206 (3216X08L)")
      (description "Resistor")
      (fields (field (name "TOLERANCE") "5%") (field (name "POWER") "1/4 W"))
      (libsource (lib "AltiumLib1") (part "Resistor"))
    )
    (comp (ref "R22")
      (value "10K")
      (footprint "RES 1206 (3216X08L)")
      (description "Resistor")
      (fields (field (name "TOLERANCE") "5%") (field (name "POWER") "1/4 W"))
      (libsource (lib "AltiumLib1") (part "Resistor"))
    )
    (comp (ref "R23")
      (value "10K")
      (footprint "RES 1206 (3216X08L)")
      (description "Resistor")
      (fields (field (name "TOLERANCE") "5%") (field (name "POWER") "1/4 W"))
      (libsource (lib "AltiumLib1") (part "Resistor"))
    )
    (comp (ref "R24")
      (value "10K")
      (footprint "RES 1206 (3216X08L)")
      (description "Resistor")
      (fields (field (name "TOLERANCE") "5%") (field (name "POWER") "1/4 W"))
      (libsource (lib "AltiumLib1") (part "Resistor"))
    )
    (comp (ref "R25")
      (value "10K")
      (footprint "RES 1206 (3216X08L)")
      (description "Resistor")
      (fields (field (name "TOLERANCE") "5%") (field (name "POWER") "1/4 W"))
      (libsource (lib "AltiumLib1") (part "Resistor"))
    )
    (comp (ref "R26")
      (value "10K")
      (footprint "RES 1206 (3216X08L)")
      (description "Resistor")
      (fields (field (name "TOLERANCE") "5%") (field (name "POWER") "1/4 W"))
      (libsource (lib "AltiumLib1") (part "Resistor"))
    )
    (comp (ref "R27")
      (value "10K")
      (footprint "RES 1206 (3216X08L)")
      (description "Resistor")
      (fields (field (name "TOLERANCE") "5%") (field (name "POWER") "1/4 W"))
      (libsource (lib "AltiumLib1") (part "Resistor"))
    )
    (comp (ref "R28")
      (value "10K")
      (footprint "RES 1206 (3216X08L)")
      (description "Resistor")
      (fields (field (name "TOLERANCE") "5%") (field (name "POWER") "1/4 W"))
      (libsource (lib "AltiumLib1") (part "Resistor"))
    )
    (comp (ref "R29")
      (value "10K")
      (footprint "RES 1206 (3216X08L)")
      (description "Resistor")
      (fields (field (name "TOLERANCE") "5%") (field (name "POWER") "1/4 W"))
      (libsource (lib "AltiumLib1") (part "Resistor"))
    )
    (comp (ref "R30")
      (value "10K")
      (footprint "RES 1206 (3216X08L)")
      (description "Resistor")
      (fields (field (name "TOLERANCE") "5%") (field (name "POWER") "1/4 W"))
      (libsource (lib "AltiumLib1") (part "Resistor"))
    )
    (comp (ref "R31")
      (value "10K")
      (footprint "RES 1206 (3216X08L)")
      (description "Resistor")
      (fields (field (name "TOLERANCE") "5%") (field (name "POWER") "1/4 W"))
      (libsource (lib "AltiumLib1") (part "Resistor"))
    )
    (comp (ref "R32")
      (value "10K")
      (footprint "RES 1206 (3216X08L)")
      (description "Resistor")
      (fields (field (name "TOLERANCE") "5%") (field (name "POWER") "1/4 W"))
      (libsource (lib "AltiumLib1") (part "Resistor"))
    )
    (comp (ref "R33")
      (value "10K")
      (footprint "RES 1206 (3216X08L)")
      (description "Resistor")
      (fields (field (name "TOLERANCE") "5%") (field (name "POWER") "1/4 W"))
      (libsource (lib "AltiumLib1") (part "Resistor"))
    )
    (comp (ref "R34")
      (value "10K")
      (footprint "RES 1206 (3216X08L)")
      (description "Resistor")
      (fields (field (name "TOLERANCE") "5%") (field (name "POWER") "1/4 W"))
      (libsource (lib "AltiumLib1") (part "Resistor"))
    )
    (comp (ref "R35")
      (value "10K")
      (footprint "RES 1206 (3216X08L)")
      (description "Resistor")
      (fields (field (name "TOLERANCE") "5%") (field (name "POWER") "1/4 W"))
      (libsource (lib "AltiumLib1") (part "Resistor"))
    )
    (comp (ref "R36")
      (value "10K")
      (footprint "RES 1206 (3216X08L)")
      (description "Resistor")
      (fields (field (name "TOLERANCE") "5%") (field (name "POWER") "1/4 W"))
      (libsource (lib "AltiumLib1") (part "Resistor"))
    )
    (comp (ref "R37")
      (value "10K")
      (footprint "RES 1206 (3216X08L)")
      (description "Resistor")
      (fields (field (name "TOLERANCE") "5%") (field (name "POWER") "1/4 W"))
      (libsource (lib "AltiumLib1") (part "Resistor"))
    )
    (comp (ref "R38")
      (value "10K")
      (footprint "RES 1206 (3216X08L)")
      (description "Resistor")
      (fields (field (name "TOLERANCE") "5%") (field (name "POWER") "1/4 W"))
      (libsource (lib "AltiumLib1") (part "Resistor"))
    )
    (comp (ref "R39")
      (value "10K")
      (footprint "RES 1206 (3216X08L)")
      (description "Resistor")
      (fields (field (name "TOLERANCE") "5%") (field (name "POWER") "1/4 W"))
      (libsource (lib "AltiumLib1") (part "Resistor"))
    )
    (comp (ref "R40")
      (value "10K")
      (footprint "RES 1206 (3216X08L)")
      (description "Resistor")
      (fields (field (name "TOLERANCE") "5%") (field (name "POWER") "1/4 W"))
      (libsource (lib "AltiumLib1") (part "Resistor"))
    )
    (comp (ref "R41")
      (value "10K")
      (footprint "RES 1206 (3216X08L)")
      (description "Resistor")
      (fields (field (name "TOLERANCE") "5%") (field (name "POWER") "1/4 W"))
      (libsource (lib "AltiumLib1") (part "Resistor"))
    )
    (comp (ref "R42")
      (value "10K")
      (footprint "RES 1206 (3216X08L)")
      (description "Resistor")
      (fields (field (name "TOLERANCE") "5%") (field (name "POWER") "1/4 W"))
      (libsource (lib "AltiumLib1") (part "Resistor"))
    )
  )
  (nets
    (net (code "1") (name "/+") (class "Default")
      (node (ref "D127") (pin "1") (pinfunction "A_1") (pintype "passive"))
      (node (ref "P1") (pin "1") (pinfunction "1_1") (pintype "passive"))
    )
    (net (code "2") (name "/-") (class "Default")
      (node (ref "P1") (pin "10") (pinfunction "10_10") (pintype "passive"))
    )
    (net (code "3") (name "/1") (class "Default")
      (node (ref "P1") (pin "9") (pinfunction "9_9") (pintype "passive"))
    )
    (net (code "4") (name "/A") (class "Default")
      (node (ref "P1") (pin "2") (pinfunction "2_2") (pintype "passive"))
      (node (ref "R1") (pin "1") (pinfunction "1_1") (pintype "passive"))
      (node (ref "R13") (pin "1") (pinfunction "1_1") (pintype "passive"))
      (node (ref "R17") (pin "1") (pinfunction "1_1") (pintype "passive"))
      (node (ref "R21") (pin "1") (pinfunction "1_1") (pintype "passive"))
      (node (ref "R5") (pin "1") (pinfunction "1_1") (pintype "passive"))
      (node (ref "R9") (pin "1") (pinfunction "1_1") (pintype "passive"))
    )
    (net (code "5") (name "/B") (class "Default")
      (node (ref "P1") (pin "3") (pinfunction "3_3") (pintype "passive"))
    )
    (net (code "6") (name "/C") (class "Default")
      (node (ref "P1") (pin "4") (pinfunction "4_4") (pintype "passive"))
      (node (ref "R11") (pin "1") (pinfunction "1_1") (pintype "passive"))
      (node (ref "R15") (pin "1") (pinfunction "1_1") (pintype "passive"))
      (node (ref "R19") (pin "1") (pinfunction "1_1") (pintype "passive"))
      (node (ref "R23") (pin "1") (pinfunction "1_1") (pintype "passive"))
      (node (ref "R3") (pin "1") (pinfunction "1_1") (pintype "passive"))
      (node (ref "R7") (pin "1") (pinfunction "1_1") (pintype "passive"))
    )
    (net (code "7") (name "/D") (class "Default")
      (node (ref "P1") (pin "5") (pinfunction "5_5") (pintype "passive"))
      (node (ref "R12") (pin "1") (pinfunction "1_1") (pintype "passive"))
      (node (ref "R16") (pin "1") (pinfunction "1_1") (pintype "passive"))
      (node (ref "R20") (pin "1") (pinfunction "1_1") (pintype "passive"))
      (node (ref "R24") (pin "1") (pinfunction "1_1") (pintype "passive"))
      (node (ref "R4") (pin "1") (pinfunction "1_1") (pintype "passive"))
      (node (ref "R8") (pin "1") (pinfunction "1_1") (pintype "passive"))
    )
    (net (code "8") (name "/DN") (class "Default")
      (node (ref "P1") (pin "12") (pinfunction "12_12") (pintype "passive"))
    )
    (net (code "9") (name "/E") (class "Default")
      (node (ref "P1") (pin "6") (pinfunction "6_6") (pintype "passive"))
    )
    (net (code "10") (name "/F") (class "Default")
      (node (ref "P1") (pin "7") (pinfunction "7_7") (pintype "passive"))
      (node (ref "R26") (pin "1") (pinfunction "1_1") (pintype "passive"))
      (node (ref "R29") (pin "1") (pinfunction "1_1") (pintype "passive"))
      (node (ref "R32") (pin "1") (pinfunction "1_1") (pintype "passive"))
      (node (ref "R35") (pin "1") (pinfunction "1_1") (pintype "passive"))
      (node (ref "R38") (pin "1") (pinfunction "1_1") (pintype "passive"))
      (node (ref "R41") (pin "1") (pinfunction "1_1") (pintype "passive"))
    )
    (net (code "11") (name "/G") (class "Default")
      (node (ref "P1") (pin "8") (pinfunction "8_8") (pintype "passive"))
    )
    (net (code "12") (name "/UP") (class "Default")
      (node (ref "P1") (pin "11") (pinfunction "11_11") (pintype "passive"))
    )
    (net (code "13") (name "Net-(D1-K)") (class "Default")
      (node (ref "D1") (pin "2") (pinfunction "K_2") (pintype "passive"))
      (node (ref "D2") (pin "1") (pinfunction "A_1") (pintype "passive"))
    )
    (net (code "14") (name "Net-(D2-K)") (class "Default")
      (node (ref "D2") (pin "2") (pinfunction "K_2") (pintype "passive"))
      (node (ref "D3") (pin "1") (pinfunction "A_1") (pintype "passive"))
    )
    (net (code "15") (name "Net-(D3-K)") (class "Default")
      (node (ref "D3") (pin "2") (pinfunction "K_2") (pintype "passive"))
      (node (ref "R1") (pin "2") (pinfunction "2_2") (pintype "passive"))
    )
    (net (code "16") (name "Net-(D4-K)") (class "Default")
      (node (ref "D4") (pin "2") (pinfunction "K_2") (pintype "passive"))
      (node (ref "D5") (pin "1") (pinfunction "A_1") (pintype "passive"))
    )
    (net (code "17") (name "Net-(D5-K)") (class "Default")
      (node (ref "D5") (pin "2") (pinfunction "K_2") (pintype "passive"))
      (node (ref "D6") (pin "1") (pinfunction "A_1") (pintype "passive"))
    )
    (net (code "18") (name "Net-(D6-K)") (class "Default")
      (node (ref "D6") (pin "2") (pinfunction "K_2") (pintype "passive"))
      (node (ref "R2") (pin "2") (pinfunction "2_2") (pintype "passive"))
    )
    (net (code "19") (name "Net-(D7-K)") (class "Default")
      (node (ref "D7") (pin "2") (pinfunction "K_2") (pintype "passive"))
      (node (ref "D8") (pin "1") (pinfunction "A_1") (pintype "passive"))
    )
    (net (code "20") (name "Net-(D8-K)") (class "Default")
      (node (ref "D8") (pin "2") (pinfunction "K_2") (pintype "passive"))
      (node (ref "D9") (pin "1") (pinfunction "A_1") (pintype "passive"))
    )
    (net (code "21") (name "Net-(D9-K)") (class "Default")
      (node (ref "D9") (pin "2") (pinfunction "K_2") (pintype "passive"))
      (node (ref "R3") (pin "2") (pinfunction "2_2") (pintype "passive"))
    )
    (net (code "22") (name "Net-(D10-K)") (class "Default")
      (node (ref "D10") (pin "2") (pinfunction "K_2") (pintype "passive"))
      (node (ref "D11") (pin "1") (pinfunction "A_1") (pintype "passive"))
    )
    (net (code "23") (name "Net-(D11-K)") (class "Default")
      (node (ref "D11") (pin "2") (pinfunction "K_2") (pintype "passive"))
      (node (ref "D12") (pin "1") (pinfunction "A_1") (pintype "passive"))
    )
    (net (code "24") (name "Net-(D12-K)") (class "Default")
      (node (ref "D12") (pin "2") (pinfunction "K_2") (pintype "passive"))
      (node (ref "R4") (pin "2") (pinfunction "2_2") (pintype "passive"))
    )
    (net (code "25") (name "Net-(D13-K)") (class "Default")
      (node (ref "D13") (pin "2") (pinfunction "K_2") (pintype "passive"))
      (node (ref "D14") (pin "1") (pinfunction "A_1") (pintype "passive"))
    )
    (net (code "26") (name "Net-(D14-K)") (class "Default")
      (node (ref "D14") (pin "2") (pinfunction "K_2") (pintype "passive"))
      (node (ref "D15") (pin "1") (pinfunction "A_1") (pintype "passive"))
    )
    (net (code "27") (name "Net-(D15-K)") (class "Default")
      (node (ref "D15") (pin "2") (pinfunction "K_2") (pintype "passive"))
      (node (ref "R5") (pin "2") (pinfunction "2_2") (pintype "passive"))
    )
    (net (code "28") (name "Net-(D16-K)") (class "Default")
      (node (ref "D16") (pin "2") (pinfunction "K_2") (pintype "passive"))
      (node (ref "D17") (pin "1") (pinfunction "A_1") (pintype "passive"))
    )
    (net (code "29") (name "Net-(D17-K)") (class "Default")
      (node (ref "D17") (pin "2") (pinfunction "K_2") (pintype "passive"))
      (node (ref "D18") (pin "1") (pinfunction "A_1") (pintype "passive"))
    )
    (net (code "30") (name "Net-(D18-K)") (class "Default")
      (node (ref "D18") (pin "2") (pinfunction "K_2") (pintype "passive"))
      (node (ref "R6") (pin "2") (pinfunction "2_2") (pintype "passive"))
    )
    (net (code "31") (name "Net-(D19-K)") (class "Default")
      (node (ref "D19") (pin "2") (pinfunction "K_2") (pintype "passive"))
      (node (ref "D20") (pin "1") (pinfunction "A_1") (pintype "passive"))
    )
    (net (code "32") (name "Net-(D20-K)") (class "Default")
      (node (ref "D20") (pin "2") (pinfunction "K_2") (pintype "passive"))
      (node (ref "D21") (pin "1") (pinfunction "A_1") (pintype "passive"))
    )
    (net (code "33") (name "Net-(D21-K)") (class "Default")
      (node (ref "D21") (pin "2") (pinfunction "K_2") (pintype "passive"))
      (node (ref "R7") (pin "2") (pinfunction "2_2") (pintype "passive"))
    )
    (net (code "34") (name "Net-(D22-K)") (class "Default")
      (node (ref "D22") (pin "2") (pinfunction "K_2") (pintype "passive"))
      (node (ref "D23") (pin "1") (pinfunction "A_1") (pintype "passive"))
    )
    (net (code "35") (name "Net-(D23-K)") (class "Default")
      (node (ref "D23") (pin "2") (pinfunction "K_2") (pintype "passive"))
      (node (ref "D24") (pin "1") (pinfunction "A_1") (pintype "passive"))
    )
    (net (code "36") (name "Net-(D24-K)") (class "Default")
      (node (ref "D24") (pin "2") (pinfunction "K_2") (pintype "passive"))
      (node (ref "R8") (pin "2") (pinfunction "2_2") (pintype "passive"))
    )
    (net (code "37") (name "Net-(D25-K)") (class "Default")
      (node (ref "D25") (pin "2") (pinfunction "K_2") (pintype "passive"))
      (node (ref "D26") (pin "1") (pinfunction "A_1") (pintype "passive"))
    )
    (net (code "38") (name "Net-(D26-K)") (class "Default")
      (node (ref "D26") (pin "2") (pinfunction "K_2") (pintype "passive"))
      (node (ref "D27") (pin "1") (pinfunction "A_1") (pintype "passive"))
    )
    (net (code "39") (name "Net-(D27-K)") (class "Default")
      (node (ref "D27") (pin "2") (pinfunction "K_2") (pintype "passive"))
      (node (ref "R9") (pin "2") (pinfunction "2_2") (pintype "passive"))
    )
    (net (code "40") (name "Net-(D28-K)") (class "Default")
      (node (ref "D28") (pin "2") (pinfunction "K_2") (pintype "passive"))
      (node (ref "D29") (pin "1") (pinfunction "A_1") (pintype "passive"))
    )
    (net (code "41") (name "Net-(D29-K)") (class "Default")
      (node (ref "D29") (pin "2") (pinfunction "K_2") (pintype "passive"))
      (node (ref "D30") (pin "1") (pinfunction "A_1") (pintype "passive"))
    )
    (net (code "42") (name "Net-(D30-K)") (class "Default")
      (node (ref "D30") (pin "2") (pinfunction "K_2") (pintype "passive"))
      (node (ref "R10") (pin "2") (pinfunction "2_2") (pintype "passive"))
    )
    (net (code "43") (name "Net-(D31-K)") (class "Default")
      (node (ref "D31") (pin "2") (pinfunction "K_2") (pintype "passive"))
      (node (ref "D32") (pin "1") (pinfunction "A_1") (pintype "passive"))
    )
    (net (code "44") (name "Net-(D32-K)") (class "Default")
      (node (ref "D32") (pin "2") (pinfunction "K_2") (pintype "passive"))
      (node (ref "D33") (pin "1") (pinfunction "A_1") (pintype "passive"))
    )
    (net (code "45") (name "Net-(D33-K)") (class "Default")
      (node (ref "D33") (pin "2") (pinfunction "K_2") (pintype "passive"))
      (node (ref "R11") (pin "2") (pinfunction "2_2") (pintype "passive"))
    )
    (net (code "46") (name "Net-(D34-K)") (class "Default")
      (node (ref "D34") (pin "2") (pinfunction "K_2") (pintype "passive"))
      (node (ref "D35") (pin "1") (pinfunction "A_1") (pintype "passive"))
    )
    (net (code "47") (name "Net-(D35-K)") (class "Default")
      (node (ref "D35") (pin "2") (pinfunction "K_2") (pintype "passive"))
      (node (ref "D36") (pin "1") (pinfunction "A_1") (pintype "passive"))
    )
    (net (code "48") (name "Net-(D36-K)") (class "Default")
      (node (ref "D36") (pin "2") (pinfunction "K_2") (pintype "passive"))
      (node (ref "R12") (pin "2") (pinfunction "2_2") (pintype "passive"))
    )
    (net (code "49") (name "Net-(D37-K)") (class "Default")
      (node (ref "D37") (pin "2") (pinfunction "K_2") (pintype "passive"))
      (node (ref "D38") (pin "1") (pinfunction "A_1") (pintype "passive"))
    )
    (net (code "50") (name "Net-(D38-K)") (class "Default")
      (node (ref "D38") (pin "2") (pinfunction "K_2") (pintype "passive"))
      (node (ref "D39") (pin "1") (pinfunction "A_1") (pintype "passive"))
    )
    (net (code "51") (name "Net-(D39-K)") (class "Default")
      (node (ref "D39") (pin "2") (pinfunction "K_2") (pintype "passive"))
      (node (ref "R13") (pin "2") (pinfunction "2_2") (pintype "passive"))
    )
    (net (code "52") (name "Net-(D40-K)") (class "Default")
      (node (ref "D40") (pin "2") (pinfunction "K_2") (pintype "passive"))
      (node (ref "D41") (pin "1") (pinfunction "A_1") (pintype "passive"))
    )
    (net (code "53") (name "Net-(D41-K)") (class "Default")
      (node (ref "D41") (pin "2") (pinfunction "K_2") (pintype "passive"))
      (node (ref "D42") (pin "1") (pinfunction "A_1") (pintype "passive"))
    )
    (net (code "54") (name "Net-(D42-K)") (class "Default")
      (node (ref "D42") (pin "2") (pinfunction "K_2") (pintype "passive"))
      (node (ref "R14") (pin "2") (pinfunction "2_2") (pintype "passive"))
    )
    (net (code "55") (name "Net-(D43-K)") (class "Default")
      (node (ref "D43") (pin "2") (pinfunction "K_2") (pintype "passive"))
      (node (ref "D44") (pin "1") (pinfunction "A_1") (pintype "passive"))
    )
    (net (code "56") (name "Net-(D44-K)") (class "Default")
      (node (ref "D44") (pin "2") (pinfunction "K_2") (pintype "passive"))
      (node (ref "D45") (pin "1") (pinfunction "A_1") (pintype "passive"))
    )
    (net (code "57") (name "Net-(D45-K)") (class "Default")
      (node (ref "D45") (pin "2") (pinfunction "K_2") (pintype "passive"))
      (node (ref "R15") (pin "2") (pinfunction "2_2") (pintype "passive"))
    )
    (net (code "58") (name "Net-(D46-K)") (class "Default")
      (node (ref "D46") (pin "2") (pinfunction "K_2") (pintype "passive"))
      (node (ref "D47") (pin "1") (pinfunction "A_1") (pintype "passive"))
    )
    (net (code "59") (name "Net-(D47-K)") (class "Default")
      (node (ref "D47") (pin "2") (pinfunction "K_2") (pintype "passive"))
      (node (ref "D48") (pin "1") (pinfunction "A_1") (pintype "passive"))
    )
    (net (code "60") (name "Net-(D48-K)") (class "Default")
      (node (ref "D48") (pin "2") (pinfunction "K_2") (pintype "passive"))
      (node (ref "R16") (pin "2") (pinfunction "2_2") (pintype "passive"))
    )
    (net (code "61") (name "Net-(D49-K)") (class "Default")
      (node (ref "D49") (pin "2") (pinfunction "K_2") (pintype "passive"))
      (node (ref "D50") (pin "1") (pinfunction "A_1") (pintype "passive"))
    )
    (net (code "62") (name "Net-(D50-K)") (class "Default")
      (node (ref "D50") (pin "2") (pinfunction "K_2") (pintype "passive"))
      (node (ref "D51") (pin "1") (pinfunction "A_1") (pintype "passive"))
    )
    (net (code "63") (name "Net-(D51-K)") (class "Default")
      (node (ref "D51") (pin "2") (pinfunction "K_2") (pintype "passive"))
      (node (ref "R17") (pin "2") (pinfunction "2_2") (pintype "passive"))
    )
    (net (code "64") (name "Net-(D52-K)") (class "Default")
      (node (ref "D52") (pin "2") (pinfunction "K_2") (pintype "passive"))
      (node (ref "D53") (pin "1") (pinfunction "A_1") (pintype "passive"))
    )
    (net (code "65") (name "Net-(D53-K)") (class "Default")
      (node (ref "D53") (pin "2") (pinfunction "K_2") (pintype "passive"))
      (node (ref "D54") (pin "1") (pinfunction "A_1") (pintype "passive"))
    )
    (net (code "66") (name "Net-(D54-K)") (class "Default")
      (node (ref "D54") (pin "2") (pinfunction "K_2") (pintype "passive"))
      (node (ref "R18") (pin "2") (pinfunction "2_2") (pintype "passive"))
    )
    (net (code "67") (name "Net-(D55-K)") (class "Default")
      (node (ref "D55") (pin "2") (pinfunction "K_2") (pintype "passive"))
      (node (ref "D56") (pin "1") (pinfunction "A_1") (pintype "passive"))
    )
    (net (code "68") (name "Net-(D56-K)") (class "Default")
      (node (ref "D56") (pin "2") (pinfunction "K_2") (pintype "passive"))
      (node (ref "D57") (pin "1") (pinfunction "A_1") (pintype "passive"))
    )
    (net (code "69") (name "Net-(D57-K)") (class "Default")
      (node (ref "D57") (pin "2") (pinfunction "K_2") (pintype "passive"))
      (node (ref "R19") (pin "2") (pinfunction "2_2") (pintype "passive"))
    )
    (net (code "70") (name "Net-(D58-K)") (class "Default")
      (node (ref "D58") (pin "2") (pinfunction "K_2") (pintype "passive"))
      (node (ref "D59") (pin "1") (pinfunction "A_1") (pintype "passive"))
    )
    (net (code "71") (name "Net-(D59-K)") (class "Default")
      (node (ref "D59") (pin "2") (pinfunction "K_2") (pintype "passive"))
      (node (ref "D60") (pin "1") (pinfunction "A_1") (pintype "passive"))
    )
    (net (code "72") (name "Net-(D60-K)") (class "Default")
      (node (ref "D60") (pin "2") (pinfunction "K_2") (pintype "passive"))
      (node (ref "R20") (pin "2") (pinfunction "2_2") (pintype "passive"))
    )
    (net (code "73") (name "Net-(D61-K)") (class "Default")
      (node (ref "D61") (pin "2") (pinfunction "K_2") (pintype "passive"))
      (node (ref "D62") (pin "1") (pinfunction "A_1") (pintype "passive"))
    )
    (net (code "74") (name "Net-(D62-K)") (class "Default")
      (node (ref "D62") (pin "2") (pinfunction "K_2") (pintype "passive"))
      (node (ref "D63") (pin "1") (pinfunction "A_1") (pintype "passive"))
    )
    (net (code "75") (name "Net-(D63-K)") (class "Default")
      (node (ref "D63") (pin "2") (pinfunction "K_2") (pintype "passive"))
      (node (ref "R21") (pin "2") (pinfunction "2_2") (pintype "passive"))
    )
    (net (code "76") (name "Net-(D64-K)") (class "Default")
      (node (ref "D64") (pin "2") (pinfunction "K_2") (pintype "passive"))
      (node (ref "D65") (pin "1") (pinfunction "A_1") (pintype "passive"))
    )
    (net (code "77") (name "Net-(D65-K)") (class "Default")
      (node (ref "D65") (pin "2") (pinfunction "K_2") (pintype "passive"))
      (node (ref "D66") (pin "1") (pinfunction "A_1") (pintype "passive"))
    )
    (net (code "78") (name "Net-(D66-K)") (class "Default")
      (node (ref "D66") (pin "2") (pinfunction "K_2") (pintype "passive"))
      (node (ref "R22") (pin "2") (pinfunction "2_2") (pintype "passive"))
    )
    (net (code "79") (name "Net-(D67-K)") (class "Default")
      (node (ref "D67") (pin "2") (pinfunction "K_2") (pintype "passive"))
      (node (ref "D68") (pin "1") (pinfunction "A_1") (pintype "passive"))
    )
    (net (code "80") (name "Net-(D68-K)") (class "Default")
      (node (ref "D68") (pin "2") (pinfunction "K_2") (pintype "passive"))
      (node (ref "D69") (pin "1") (pinfunction "A_1") (pintype "passive"))
    )
    (net (code "81") (name "Net-(D69-K)") (class "Default")
      (node (ref "D69") (pin "2") (pinfunction "K_2") (pintype "passive"))
      (node (ref "R23") (pin "2") (pinfunction "2_2") (pintype "passive"))
    )
    (net (code "82") (name "Net-(D70-K)") (class "Default")
      (node (ref "D70") (pin "2") (pinfunction "K_2") (pintype "passive"))
      (node (ref "D71") (pin "1") (pinfunction "A_1") (pintype "passive"))
    )
    (net (code "83") (name "Net-(D71-K)") (class "Default")
      (node (ref "D71") (pin "2") (pinfunction "K_2") (pintype "passive"))
      (node (ref "D72") (pin "1") (pinfunction "A_1") (pintype "passive"))
    )
    (net (code "84") (name "Net-(D72-K)") (class "Default")
      (node (ref "D72") (pin "2") (pinfunction "K_2") (pintype "passive"))
      (node (ref "R24") (pin "2") (pinfunction "2_2") (pintype "passive"))
    )
    (net (code "85") (name "Net-(D73-K)") (class "Default")
      (node (ref "D73") (pin "2") (pinfunction "K_2") (pintype "passive"))
      (node (ref "D74") (pin "1") (pinfunction "A_1") (pintype "passive"))
    )
    (net (code "86") (name "Net-(D74-K)") (class "Default")
      (node (ref "D74") (pin "2") (pinfunction "K_2") (pintype "passive"))
      (node (ref "D75") (pin "1") (pinfunction "A_1") (pintype "passive"))
    )
    (net (code "87") (name "Net-(D75-K)") (class "Default")
      (node (ref "D75") (pin "2") (pinfunction "K_2") (pintype "passive"))
      (node (ref "R25") (pin "2") (pinfunction "2_2") (pintype "passive"))
    )
    (net (code "88") (name "Net-(D76-K)") (class "Default")
      (node (ref "D76") (pin "2") (pinfunction "K_2") (pintype "passive"))
      (node (ref "D77") (pin "1") (pinfunction "A_1") (pintype "passive"))
    )
    (net (code "89") (name "Net-(D77-K)") (class "Default")
      (node (ref "D77") (pin "2") (pinfunction "K_2") (pintype "passive"))
      (node (ref "D78") (pin "1") (pinfunction "A_1") (pintype "passive"))
    )
    (net (code "90") (name "Net-(D78-K)") (class "Default")
      (node (ref "D78") (pin "2") (pinfunction "K_2") (pintype "passive"))
      (node (ref "R26") (pin "2") (pinfunction "2_2") (pintype "passive"))
    )
    (net (code "91") (name "Net-(D79-K)") (class "Default")
      (node (ref "D79") (pin "2") (pinfunction "K_2") (pintype "passive"))
      (node (ref "D80") (pin "1") (pinfunction "A_1") (pintype "passive"))
    )
    (net (code "92") (name "Net-(D80-K)") (class "Default")
      (node (ref "D80") (pin "2") (pinfunction "K_2") (pintype "passive"))
      (node (ref "D81") (pin "1") (pinfunction "A_1") (pintype "passive"))
    )
    (net (code "93") (name "Net-(D81-K)") (class "Default")
      (node (ref "D81") (pin "2") (pinfunction "K_2") (pintype "passive"))
      (node (ref "R27") (pin "2") (pinfunction "2_2") (pintype "passive"))
    )
    (net (code "94") (name "Net-(D82-K)") (class "Default")
      (node (ref "D82") (pin "2") (pinfunction "K_2") (pintype "passive"))
      (node (ref "D83") (pin "1") (pinfunction "A_1") (pintype "passive"))
    )
    (net (code "95") (name "Net-(D83-K)") (class "Default")
      (node (ref "D83") (pin "2") (pinfunction "K_2") (pintype "passive"))
      (node (ref "D84") (pin "1") (pinfunction "A_1") (pintype "passive"))
    )
    (net (code "96") (name "Net-(D84-K)") (class "Default")
      (node (ref "D84") (pin "2") (pinfunction "K_2") (pintype "passive"))
      (node (ref "R28") (pin "2") (pinfunction "2_2") (pintype "passive"))
    )
    (net (code "97") (name "Net-(D85-K)") (class "Default")
      (node (ref "D85") (pin "2") (pinfunction "K_2") (pintype "passive"))
      (node (ref "D86") (pin "1") (pinfunction "A_1") (pintype "passive"))
    )
    (net (code "98") (name "Net-(D86-K)") (class "Default")
      (node (ref "D86") (pin "2") (pinfunction "K_2") (pintype "passive"))
      (node (ref "D87") (pin "1") (pinfunction "A_1") (pintype "passive"))
    )
    (net (code "99") (name "Net-(D87-K)") (class "Default")
      (node (ref "D87") (pin "2") (pinfunction "K_2") (pintype "passive"))
      (node (ref "R29") (pin "2") (pinfunction "2_2") (pintype "passive"))
    )
    (net (code "100") (name "Net-(D88-K)") (class "Default")
      (node (ref "D88") (pin "2") (pinfunction "K_2") (pintype "passive"))
      (node (ref "D89") (pin "1") (pinfunction "A_1") (pintype "passive"))
    )
    (net (code "101") (name "Net-(D89-K)") (class "Default")
      (node (ref "D89") (pin "2") (pinfunction "K_2") (pintype "passive"))
      (node (ref "D90") (pin "1") (pinfunction "A_1") (pintype "passive"))
    )
    (net (code "102") (name "Net-(D90-K)") (class "Default")
      (node (ref "D90") (pin "2") (pinfunction "K_2") (pintype "passive"))
      (node (ref "R30") (pin "2") (pinfunction "2_2") (pintype "passive"))
    )
    (net (code "103") (name "Net-(D91-K)") (class "Default")
      (node (ref "D91") (pin "2") (pinfunction "K_2") (pintype "passive"))
      (node (ref "D92") (pin "1") (pinfunction "A_1") (pintype "passive"))
    )
    (net (code "104") (name "Net-(D92-K)") (class "Default")
      (node (ref "D92") (pin "2") (pinfunction "K_2") (pintype "passive"))
      (node (ref "D93") (pin "1") (pinfunction "A_1") (pintype "passive"))
    )
    (net (code "105") (name "Net-(D93-K)") (class "Default")
      (node (ref "D93") (pin "2") (pinfunction "K_2") (pintype "passive"))
      (node (ref "R31") (pin "2") (pinfunction "2_2") (pintype "passive"))
    )
    (net (code "106") (name "Net-(D94-K)") (class "Default")
      (node (ref "D94") (pin "2") (pinfunction "K_2") (pintype "passive"))
      (node (ref "D95") (pin "1") (pinfunction "A_1") (pintype "passive"))
    )
    (net (code "107") (name "Net-(D95-K)") (class "Default")
      (node (ref "D95") (pin "2") (pinfunction "K_2") (pintype "passive"))
      (node (ref "D96") (pin "1") (pinfunction "A_1") (pintype "passive"))
    )
    (net (code "108") (name "Net-(D96-K)") (class "Default")
      (node (ref "D96") (pin "2") (pinfunction "K_2") (pintype "passive"))
      (node (ref "R32") (pin "2") (pinfunction "2_2") (pintype "passive"))
    )
    (net (code "109") (name "Net-(D97-K)") (class "Default")
      (node (ref "D97") (pin "2") (pinfunction "K_2") (pintype "passive"))
      (node (ref "D98") (pin "1") (pinfunction "A_1") (pintype "passive"))
    )
    (net (code "110") (name "Net-(D98-K)") (class "Default")
      (node (ref "D98") (pin "2") (pinfunction "K_2") (pintype "passive"))
      (node (ref "D99") (pin "1") (pinfunction "A_1") (pintype "passive"))
    )
    (net (code "111") (name "Net-(D99-K)") (class "Default")
      (node (ref "D99") (pin "2") (pinfunction "K_2") (pintype "passive"))
      (node (ref "R33") (pin "2") (pinfunction "2_2") (pintype "passive"))
    )
    (net (code "112") (name "Net-(D100-K)") (class "Default")
      (node (ref "D100") (pin "2") (pinfunction "K_2") (pintype "passive"))
      (node (ref "D101") (pin "1") (pinfunction "A_1") (pintype "passive"))
    )
    (net (code "113") (name "Net-(D101-K)") (class "Default")
      (node (ref "D101") (pin "2") (pinfunction "K_2") (pintype "passive"))
      (node (ref "D102") (pin "1") (pinfunction "A_1") (pintype "passive"))
    )
    (net (code "114") (name "Net-(D102-K)") (class "Default")
      (node (ref "D102") (pin "2") (pinfunction "K_2") (pintype "passive"))
      (node (ref "R34") (pin "2") (pinfunction "2_2") (pintype "passive"))
    )
    (net (code "115") (name "Net-(D103-K)") (class "Default")
      (node (ref "D103") (pin "2") (pinfunction "K_2") (pintype "passive"))
      (node (ref "D104") (pin "1") (pinfunction "A_1") (pintype "passive"))
    )
    (net (code "116") (name "Net-(D104-K)") (class "Default")
      (node (ref "D104") (pin "2") (pinfunction "K_2") (pintype "passive"))
      (node (ref "D105") (pin "1") (pinfunction "A_1") (pintype "passive"))
    )
    (net (code "117") (name "Net-(D105-K)") (class "Default")
      (node (ref "D105") (pin "2") (pinfunction "K_2") (pintype "passive"))
      (node (ref "R35") (pin "2") (pinfunction "2_2") (pintype "passive"))
    )
    (net (code "118") (name "Net-(D106-K)") (class "Default")
      (node (ref "D106") (pin "2") (pinfunction "K_2") (pintype "passive"))
      (node (ref "D107") (pin "1") (pinfunction "A_1") (pintype "passive"))
    )
    (net (code "119") (name "Net-(D107-K)") (class "Default")
      (node (ref "D107") (pin "2") (pinfunction "K_2") (pintype "passive"))
      (node (ref "D108") (pin "1") (pinfunction "A_1") (pintype "passive"))
    )
    (net (code "120") (name "Net-(D108-K)") (class "Default")
      (node (ref "D108") (pin "2") (pinfunction "K_2") (pintype "passive"))
      (node (ref "R36") (pin "2") (pinfunction "2_2") (pintype "passive"))
    )
    (net (code "121") (name "Net-(D109-K)") (class "Default")
      (node (ref "D109") (pin "2") (pinfunction "K_2") (pintype "passive"))
      (node (ref "D110") (pin "1") (pinfunction "A_1") (pintype "passive"))
    )
    (net (code "122") (name "Net-(D110-K)") (class "Default")
      (node (ref "D110") (pin "2") (pinfunction "K_2") (pintype "passive"))
      (node (ref "D111") (pin "1") (pinfunction "A_1") (pintype "passive"))
    )
    (net (code "123") (name "Net-(D111-K)") (class "Default")
      (node (ref "D111") (pin "2") (pinfunction "K_2") (pintype "passive"))
      (node (ref "R37") (pin "2") (pinfunction "2_2") (pintype "passive"))
    )
    (net (code "124") (name "Net-(D112-K)") (class "Default")
      (node (ref "D112") (pin "2") (pinfunction "K_2") (pintype "passive"))
      (node (ref "D113") (pin "1") (pinfunction "A_1") (pintype "passive"))
    )
    (net (code "125") (name "Net-(D113-K)") (class "Default")
      (node (ref "D113") (pin "2") (pinfunction "K_2") (pintype "passive"))
      (node (ref "D114") (pin "1") (pinfunction "A_1") (pintype "passive"))
    )
    (net (code "126") (name "Net-(D114-K)") (class "Default")
      (node (ref "D114") (pin "2") (pinfunction "K_2") (pintype "passive"))
      (node (ref "R38") (pin "2") (pinfunction "2_2") (pintype "passive"))
    )
    (net (code "127") (name "Net-(D115-K)") (class "Default")
      (node (ref "D115") (pin "2") (pinfunction "K_2") (pintype "passive"))
      (node (ref "D116") (pin "1") (pinfunction "A_1") (pintype "passive"))
    )
    (net (code "128") (name "Net-(D116-K)") (class "Default")
      (node (ref "D116") (pin "2") (pinfunction "K_2") (pintype "passive"))
      (node (ref "D117") (pin "1") (pinfunction "A_1") (pintype "passive"))
    )
    (net (code "129") (name "Net-(D117-K)") (class "Default")
      (node (ref "D117") (pin "2") (pinfunction "K_2") (pintype "passive"))
      (node (ref "R39") (pin "2") (pinfunction "2_2") (pintype "passive"))
    )
    (net (code "130") (name "Net-(D118-K)") (class "Default")
      (node (ref "D118") (pin "2") (pinfunction "K_2") (pintype "passive"))
      (node (ref "D119") (pin "1") (pinfunction "A_1") (pintype "passive"))
    )
    (net (code "131") (name "Net-(D119-K)") (class "Default")
      (node (ref "D119") (pin "2") (pinfunction "K_2") (pintype "passive"))
      (node (ref "D120") (pin "1") (pinfunction "A_1") (pintype "passive"))
    )
    (net (code "132") (name "Net-(D120-K)") (class "Default")
      (node (ref "D120") (pin "2") (pinfunction "K_2") (pintype "passive"))
      (node (ref "R40") (pin "2") (pinfunction "2_2") (pintype "passive"))
    )
    (net (code "133") (name "Net-(D121-K)") (class "Default")
      (node (ref "D121") (pin "2") (pinfunction "K_2") (pintype "passive"))
      (node (ref "D122") (pin "1") (pinfunction "A_1") (pintype "passive"))
    )
    (net (code "134") (name "Net-(D122-K)") (class "Default")
      (node (ref "D122") (pin "2") (pinfunction "K_2") (pintype "passive"))
      (node (ref "D123") (pin "1") (pinfunction "A_1") (pintype "passive"))
    )
    (net (code "135") (name "Net-(D123-K)") (class "Default")
      (node (ref "D123") (pin "2") (pinfunction "K_2") (pintype "passive"))
      (node (ref "R41") (pin "2") (pinfunction "2_2") (pintype "passive"))
    )
    (net (code "136") (name "Net-(D124-K)") (class "Default")
      (node (ref "D124") (pin "2") (pinfunction "K_2") (pintype "passive"))
      (node (ref "D125") (pin "1") (pinfunction "A_1") (pintype "passive"))
    )
    (net (code "137") (name "Net-(D125-K)") (class "Default")
      (node (ref "D125") (pin "2") (pinfunction "K_2") (pintype "passive"))
      (node (ref "D126") (pin "1") (pinfunction "A_1") (pintype "passive"))
    )
    (net (code "138") (name "Net-(D126-K)") (class "Default")
      (node (ref "D126") (pin "2") (pinfunction "K_2") (pintype "passive"))
      (node (ref "R42") (pin "2") (pinfunction "2_2") (pintype "passive"))
    )
    (net (code "139") (name "Net-(R10-Pad1)") (class "Default")
      (node (ref "R10") (pin "1") (pinfunction "1_1") (pintype "passive"))
      (node (ref "R14") (pin "1") (pinfunction "1_1") (pintype "passive"))
      (node (ref "R18") (pin "1") (pinfunction "1_1") (pintype "passive"))
      (node (ref "R2") (pin "1") (pinfunction "1_1") (pintype "passive"))
      (node (ref "R22") (pin "1") (pinfunction "1_1") (pintype "passive"))
      (node (ref "R6") (pin "1") (pinfunction "1_1") (pintype "passive"))
    )
    (net (code "140") (name "Net-(R25-Pad1)") (class "Default")
      (node (ref "R25") (pin "1") (pinfunction "1_1") (pintype "passive"))
      (node (ref "R28") (pin "1") (pinfunction "1_1") (pintype "passive"))
      (node (ref "R31") (pin "1") (pinfunction "1_1") (pintype "passive"))
      (node (ref "R34") (pin "1") (pinfunction "1_1") (pintype "passive"))
      (node (ref "R37") (pin "1") (pinfunction "1_1") (pintype "passive"))
      (node (ref "R40") (pin "1") (pinfunction "1_1") (pintype "passive"))
    )
    (net (code "141") (name "Net-(R27-Pad1)") (class "Default")
      (node (ref "R27") (pin "1") (pinfunction "1_1") (pintype "passive"))
      (node (ref "R30") (pin "1") (pinfunction "1_1") (pintype "passive"))
      (node (ref "R33") (pin "1") (pinfunction "1_1") (pintype "passive"))
      (node (ref "R36") (pin "1") (pinfunction "1_1") (pintype "passive"))
      (node (ref "R39") (pin "1") (pinfunction "1_1") (pintype "passive"))
      (node (ref "R42") (pin "1") (pinfunction "1_1") (pintype "passive"))
    )
    (net (code "142") (name "VCC") (class "Default")
      (node (ref "D1") (pin "1") (pinfunction "A_1") (pintype "passive"))
      (node (ref "D10") (pin "1") (pinfunction "A_1") (pintype "passive"))
      (node (ref "D100") (pin "1") (pinfunction "A_1") (pintype "passive"))
      (node (ref "D109") (pin "1") (pinfunction "A_1") (pintype "passive"))
      (node (ref "D112") (pin "1") (pinfunction "A_1") (pintype "passive"))
      (node (ref "D115") (pin "1") (pinfunction "A_1") (pintype "passive"))
      (node (ref "D118") (pin "1") (pinfunction "A_1") (pintype "passive"))
      (node (ref "D121") (pin "1") (pinfunction "A_1") (pintype "passive"))
      (node (ref "D124") (pin "1") (pinfunction "A_1") (pintype "passive"))
      (node (ref "D127") (pin "2") (pinfunction "K_2") (pintype "passive"))
      (node (ref "D13") (pin "1") (pinfunction "A_1") (pintype "passive"))
      (node (ref "D16") (pin "1") (pinfunction "A_1") (pintype "passive"))
      (node (ref "D19") (pin "1") (pinfunction "A_1") (pintype "passive"))
      (node (ref "D22") (pin "1") (pinfunction "A_1") (pintype "passive"))
      (node (ref "D25") (pin "1") (pinfunction "A_1") (pintype "passive"))
      (node (ref "D28") (pin "1") (pinfunction "A_1") (pintype "passive"))
      (node (ref "D31") (pin "1") (pinfunction "A_1") (pintype "passive"))
      (node (ref "D34") (pin "1") (pinfunction "A_1") (pintype "passive"))
      (node (ref "D4") (pin "1") (pinfunction "A_1") (pintype "passive"))
      (node (ref "D49") (pin "1") (pinfunction "A_1") (pintype "passive"))
      (node (ref "D52") (pin "1") (pinfunction "A_1") (pintype "passive"))
      (node (ref "D55") (pin "1") (pinfunction "A_1") (pintype "passive"))
      (node (ref "D58") (pin "1") (pinfunction "A_1") (pintype "passive"))
      (node (ref "D61") (pin "1") (pinfunction "A_1") (pintype "passive"))
      (node (ref "D64") (pin "1") (pinfunction "A_1") (pintype "passive"))
      (node (ref "D67") (pin "1") (pinfunction "A_1") (pintype "passive"))
      (node (ref "D7") (pin "1") (pinfunction "A_1") (pintype "passive"))
      (node (ref "D70") (pin "1") (pinfunction "A_1") (pintype "passive"))
      (node (ref "D73") (pin "1") (pinfunction "A_1") (pintype "passive"))
      (node (ref "D76") (pin "1") (pinfunction "A_1") (pintype "passive"))
      (node (ref "D79") (pin "1") (pinfunction "A_1") (pintype "passive"))
      (node (ref "D82") (pin "1") (pinfunction "A_1") (pintype "passive"))
      (node (ref "D85") (pin "1") (pinfunction "A_1") (pintype "passive"))
      (node (ref "D88") (pin "1") (pinfunction "A_1") (pintype "passive"))
      (node (ref "D91") (pin "1") (pinfunction "A_1") (pintype "passive"))
      (node (ref "D94") (pin "1") (pinfunction "A_1") (pintype "passive"))
      (node (ref "D97") (pin "1") (pinfunction "A_1") (pintype "passive"))
    )
    (net (code "143") (name "unconnected-(D37-A-Pad1)") (class "Default")
      (node (ref "D37") (pin "1") (pinfunction "A_1") (pintype "passive"))
    )
    (net (code "144") (name "unconnected-(D40-A-Pad1)") (class "Default")
      (node (ref "D40") (pin "1") (pinfunction "A_1") (pintype "passive"))
    )
    (net (code "145") (name "unconnected-(D43-A-Pad1)") (class "Default")
      (node (ref "D43") (pin "1") (pinfunction "A_1") (pintype "passive"))
    )
    (net (code "146") (name "unconnected-(D46-A-Pad1)") (class "Default")
      (node (ref "D46") (pin "1") (pinfunction "A_1") (pintype "passive"))
    )
    (net (code "147") (name "unconnected-(D103-A-Pad1)") (class "Default")
      (node (ref "D103") (pin "1") (pinfunction "A_1") (pintype "passive"))
    )
    (net (code "148") (name "unconnected-(D106-A-Pad1)") (class "Default")
      (node (ref "D106") (pin "1") (pinfunction "A_1") (pintype "passive"))
    )
  )
)
